# IMU-Module_v1_0.net
KiCad netlist of a schematic drawn in EAGLE
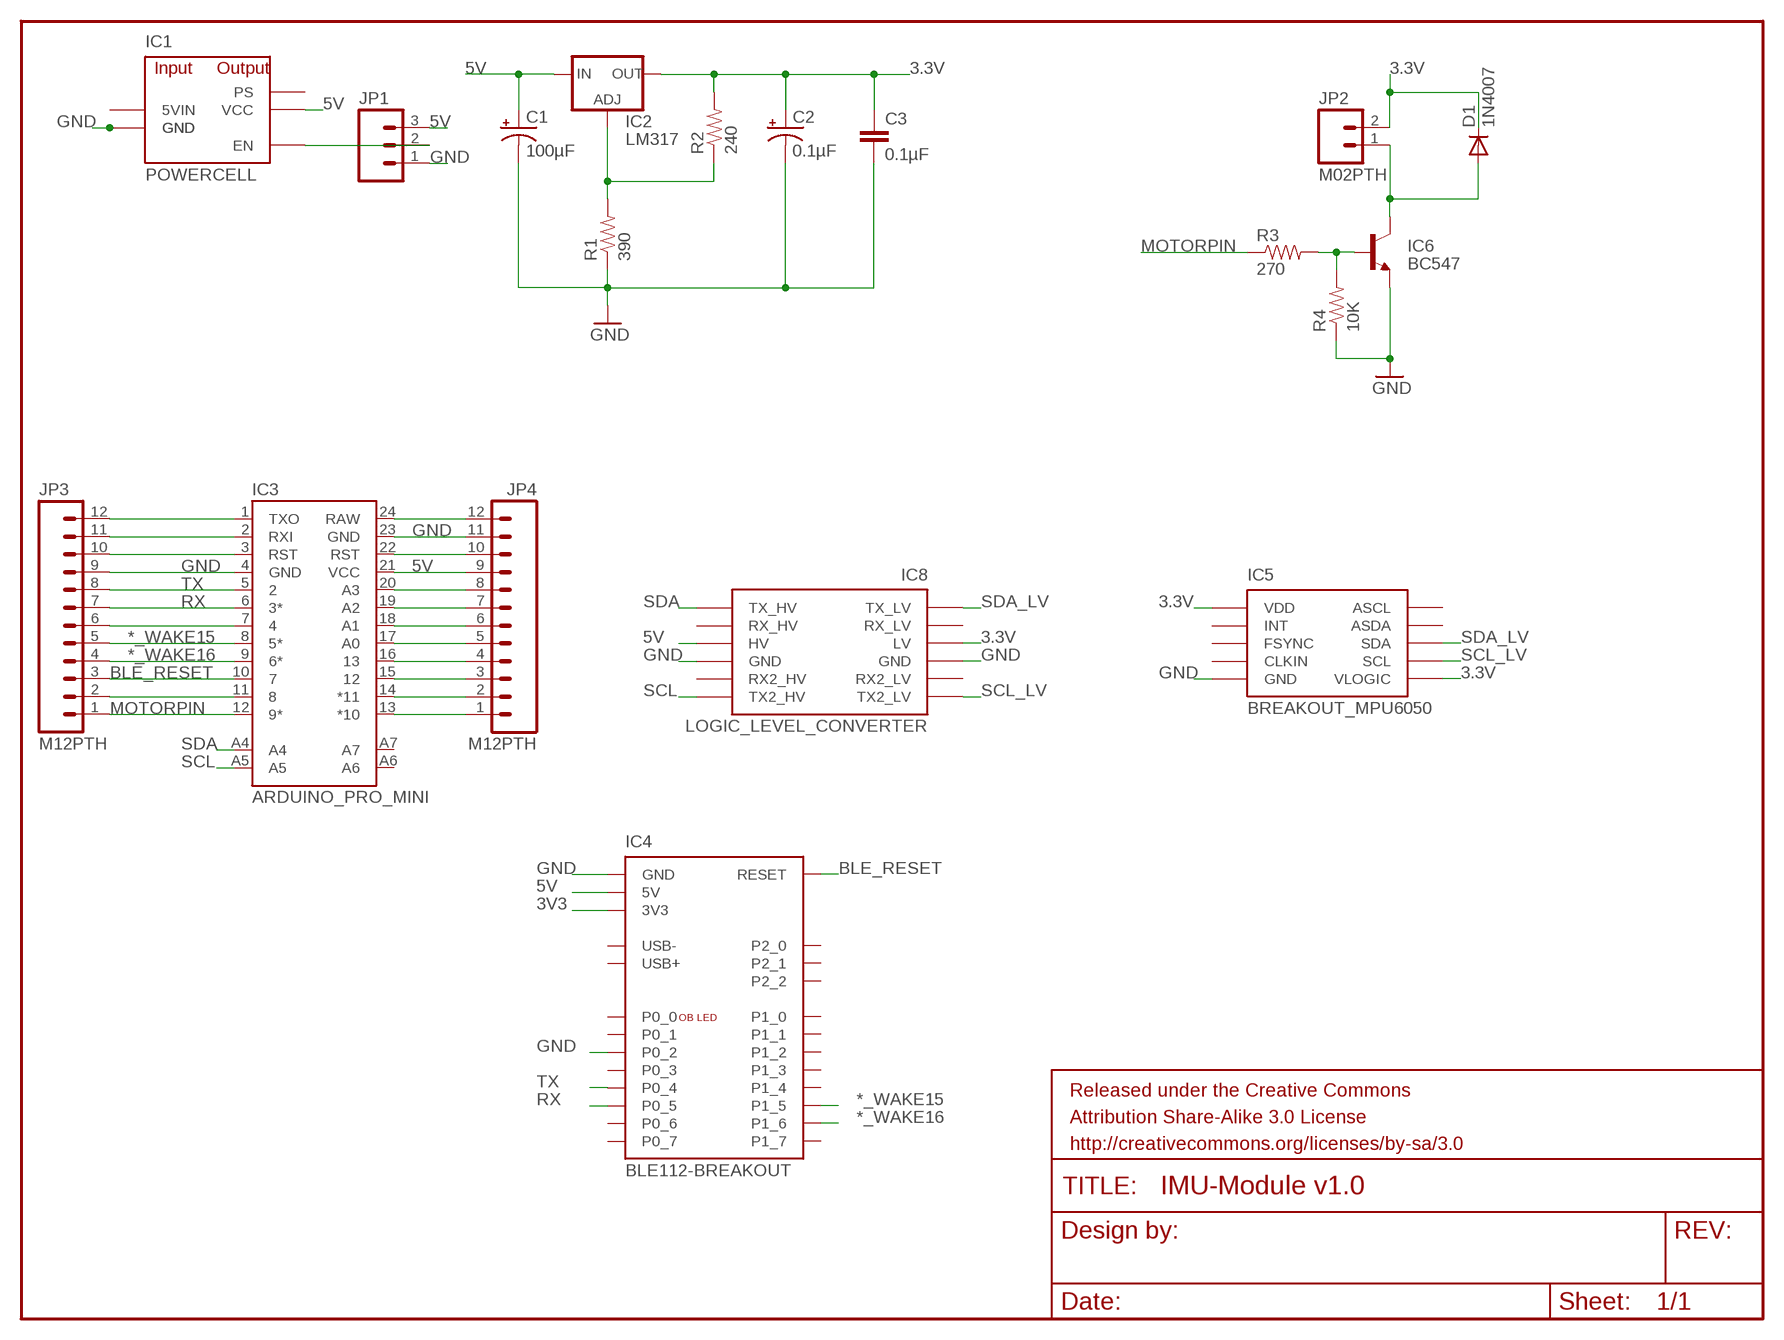
[diagram p0: schematic, sheet 1]

(export (version "E")
  (design (tool "Eeschema 10.0.6"))
  (components
    (comp (ref "C1")
      (value "100µF")
      (footprint "eagle-import:CPOL-RADIAL-100UF-25V")
      (libsource (lib "eagle-import") (part "CAP_POLPTH1"))
    )
    (comp (ref "C2")
      (value "0.1µF")
      (footprint "eagle-import:CPOL-RADIAL-10UF-25V")
      (libsource (lib "eagle-import") (part "CAP_POLPTH2"))
    )
    (comp (ref "C3")
      (value "0.1µF")
      (footprint "eagle-import:1206")
      (libsource (lib "eagle-import") (part "CAP1206"))
    )
    (comp (ref "D1")
      (value "1N4007")
      (footprint "eagle-import:DIODE-1N4001-KIT")
      (libsource (lib "eagle-import") (part "DIODE"))
    )
    (comp (ref "FRAME1")
      (value "FRAME-LETTER")
      (footprint "eagle-import:CREATIVE_COMMONS")
      (libsource (lib "eagle-import") (part "FRAME-LETTER"))
    )
    (comp (ref "IC1")
      (value "POWERCELL")
      (footprint "eagle-import:POWERCELL")
      (libsource (lib "eagle-import") (part "POWERCELL"))
    )
    (comp (ref "IC2")
      (value "LM317")
      (footprint "eagle-import:SOT223")
      (libsource (lib "eagle-import") (part "V_REG_317SMD"))
    )
    (comp (ref "IC3")
      (value "ARDUINO_PRO_MINI")
      (footprint "eagle-import:ARDUINO_PRO_MINI")
      (libsource (lib "eagle-import") (part "ARDUINO_PRO_MINI"))
    )
    (comp (ref "IC4")
      (value "BLE112-BREAKOUT")
      (footprint "eagle-import:BLE112-BREAKOUT")
      (libsource (lib "eagle-import") (part "BLE112-BREAKOUT"))
    )
    (comp (ref "IC5")
      (value "BREAKOUT_MPU6050")
      (footprint "eagle-import:BREAKOUT_MPU6050")
      (libsource (lib "eagle-import") (part "BREAKOUT_MPU6050"))
    )
    (comp (ref "IC6")
      (value "BC547")
      (footprint "eagle-import:TO-92")
      (libsource (lib "eagle-import") (part "BC547"))
    )
    (comp (ref "IC8")
      (value "LOGIC_LEVEL_CONVERTER")
      (footprint "eagle-import:LOGIC_LEVEL_CONVERTER")
      (libsource (lib "eagle-import") (part "LOGIC_LEVEL_CONVERTER"))
    )
    (comp (ref "JP1")
      (value "M03PTH")
      (footprint "eagle-import:1X03")
      (libsource (lib "eagle-import") (part "M03PTH"))
    )
    (comp (ref "JP2")
      (value "M02PTH")
      (footprint "eagle-import:1X02")
      (libsource (lib "eagle-import") (part "M02PTH"))
    )
    (comp (ref "JP3")
      (value "M12PTH")
      (footprint "eagle-import:1X12")
      (libsource (lib "eagle-import") (part "M12PTH"))
    )
    (comp (ref "JP4")
      (value "M12PTH")
      (footprint "eagle-import:1X12")
      (libsource (lib "eagle-import") (part "M12PTH"))
    )
    (comp (ref "R1")
      (value "390")
      (footprint "eagle-import:1206")
      (libsource (lib "eagle-import") (part "RESISTOR1206"))
    )
    (comp (ref "R2")
      (value "240")
      (footprint "eagle-import:1206")
      (libsource (lib "eagle-import") (part "RESISTOR1206"))
    )
    (comp (ref "R3")
      (value "270")
      (footprint "eagle-import:1206")
      (libsource (lib "eagle-import") (part "RESISTOR1206"))
    )
    (comp (ref "R4")
      (value "10K")
      (footprint "eagle-import:1206")
      (libsource (lib "eagle-import") (part "RESISTOR1206"))
    )
  )
  (nets
    (net (code "1") (name "/*_WAKE15") (class "Default")
      (node (ref "IC3") (pin "8") (pinfunction "5*_8") (pintype "bidirectional"))
      (node (ref "IC4") (pin "P15") (pinfunction "P1_5_P15") (pintype "bidirectional"))
      (node (ref "JP3") (pin "5") (pinfunction "5_5") (pintype "passive"))
    )
    (net (code "2") (name "/*_WAKE16") (class "Default")
      (node (ref "IC3") (pin "9") (pinfunction "6*_9") (pintype "bidirectional"))
      (node (ref "IC4") (pin "P16") (pinfunction "P1_6_P16") (pintype "bidirectional"))
      (node (ref "JP3") (pin "4") (pinfunction "4_4") (pintype "passive"))
    )
    (net (code "3") (name "/3.3V") (class "Default")
      (node (ref "C2") (pin "1") (pinfunction "+_1") (pintype "passive"))
      (node (ref "C3") (pin "1") (pinfunction "1_1") (pintype "passive"))
      (node (ref "D1") (pin "C") (pinfunction "C_C") (pintype "passive"))
      (node (ref "IC2") (pin "2") (pinfunction "OUT_2") (pintype "output"))
      (node (ref "IC5") (pin "VDD") (pinfunction "VDD_VDD") (pintype "power_in"))
      (node (ref "IC5") (pin "VLOGIC") (pinfunction "VLOGIC_VLOGIC") (pintype "bidirectional"))
      (node (ref "IC8") (pin "LV") (pinfunction "LV_LV") (pintype "power_in"))
      (node (ref "JP2") (pin "2") (pinfunction "2_2") (pintype "passive"))
      (node (ref "R2") (pin "2") (pinfunction "2_2") (pintype "passive"))
    )
    (net (code "4") (name "/3V3") (class "Default")
      (node (ref "IC4") (pin "3V3") (pinfunction "3V3_3V3") (pintype "power_in"))
    )
    (net (code "5") (name "/5V") (class "Default")
      (node (ref "C1") (pin "1") (pinfunction "+_1") (pintype "passive"))
      (node (ref "IC1") (pin "VCC") (pinfunction "VCC_VCC") (pintype "power_in"))
      (node (ref "IC2") (pin "3") (pinfunction "IN_3") (pintype "input"))
      (node (ref "IC3") (pin "21") (pinfunction "VCC_21") (pintype "bidirectional"))
      (node (ref "IC4") (pin "5V") (pinfunction "5V_5V") (pintype "power_in"))
      (node (ref "IC8") (pin "HV") (pinfunction "HV_HV") (pintype "power_in"))
      (node (ref "JP1") (pin "3") (pinfunction "3_3") (pintype "passive"))
      (node (ref "JP4") (pin "9") (pinfunction "9_9") (pintype "passive"))
    )
    (net (code "6") (name "/5VIN") (class "Default")
      (node (ref "IC1") (pin "5VIN") (pinfunction "5VIN_5VIN") (pintype "power_in"))
    )
    (net (code "7") (name "/BLE_RESET") (class "Default")
      (node (ref "IC3") (pin "10") (pinfunction "7_10") (pintype "bidirectional"))
      (node (ref "IC4") (pin "RESET") (pinfunction "RESET_RESET") (pintype "input"))
      (node (ref "JP3") (pin "3") (pinfunction "3_3") (pintype "passive"))
    )
    (net (code "8") (name "/MOTORPIN") (class "Default")
      (node (ref "IC3") (pin "12") (pinfunction "9*_12") (pintype "bidirectional"))
      (node (ref "JP3") (pin "1") (pinfunction "1_1") (pintype "passive"))
      (node (ref "R3") (pin "1") (pinfunction "1_1") (pintype "passive"))
    )
    (net (code "9") (name "/RX") (class "Default")
      (node (ref "IC3") (pin "6") (pinfunction "3*_6") (pintype "bidirectional"))
      (node (ref "IC4") (pin "P05") (pinfunction "P0_5_P05") (pintype "bidirectional"))
      (node (ref "JP3") (pin "7") (pinfunction "7_7") (pintype "passive"))
    )
    (net (code "10") (name "/RX2_HV") (class "Default")
      (node (ref "IC8") (pin "HV_RXI_2") (pinfunction "RX2_HV_HV_RXI_2") (pintype "power_in"))
    )
    (net (code "11") (name "/RX2_LV") (class "Default")
      (node (ref "IC8") (pin "LV_RXO_2") (pinfunction "RX2_LV_LV_RXO_2") (pintype "power_in"))
    )
    (net (code "12") (name "/RX_HV") (class "Default")
      (node (ref "IC8") (pin "HV_RXI_1") (pinfunction "RX_HV_HV_RXI_1") (pintype "power_in"))
    )
    (net (code "13") (name "/RX_LV") (class "Default")
      (node (ref "IC8") (pin "LV_RXO_1") (pinfunction "RX_LV_LV_RXO_1") (pintype "power_in"))
    )
    (net (code "14") (name "/SCL") (class "Default")
      (node (ref "IC3") (pin "A5") (pinfunction "A5_A5") (pintype "bidirectional"))
      (node (ref "IC8") (pin "HV_TXO_2") (pinfunction "TX2_HV_HV_TXO_2") (pintype "power_in"))
    )
    (net (code "15") (name "/SCL_LV") (class "Default")
      (node (ref "IC5") (pin "SCL") (pinfunction "SCL_SCL") (pintype "bidirectional"))
      (node (ref "IC8") (pin "LV_TXI_2") (pinfunction "TX2_LV_LV_TXI_2") (pintype "power_in"))
    )
    (net (code "16") (name "/SDA") (class "Default")
      (node (ref "IC3") (pin "A4") (pinfunction "A4_A4") (pintype "bidirectional"))
      (node (ref "IC8") (pin "HV_TXO_1") (pinfunction "TX_HV_HV_TXO_1") (pintype "power_in"))
    )
    (net (code "17") (name "/SDA_LV") (class "Default")
      (node (ref "IC5") (pin "SDA") (pinfunction "SDA_SDA") (pintype "bidirectional"))
      (node (ref "IC8") (pin "LV_TXI_1") (pinfunction "TX_LV_LV_TXI_1") (pintype "power_in"))
    )
    (net (code "18") (name "/TX") (class "Default")
      (node (ref "IC3") (pin "5") (pinfunction "2_5") (pintype "bidirectional"))
      (node (ref "IC4") (pin "P04") (pinfunction "P0_4_P04") (pintype "bidirectional"))
      (node (ref "JP3") (pin "8") (pinfunction "8_8") (pintype "passive"))
    )
    (net (code "19") (name "GND") (class "Default")
      (node (ref "C1") (pin "2") (pinfunction "-_2") (pintype "passive"))
      (node (ref "C2") (pin "2") (pinfunction "-_2") (pintype "passive"))
      (node (ref "C3") (pin "2") (pinfunction "2_2") (pintype "passive"))
      (node (ref "IC1") (pin "GND@1") (pinfunction "GND_GND@1") (pintype "power_in"))
      (node (ref "IC1") (pin "GND@2") (pinfunction "GND_GND@2") (pintype "power_in"))
      (node (ref "IC3") (pin "23") (pinfunction "GND_23") (pintype "bidirectional"))
      (node (ref "IC3") (pin "4") (pinfunction "GND_4") (pintype "bidirectional"))
      (node (ref "IC4") (pin "GND") (pinfunction "GND_GND") (pintype "power_in"))
      (node (ref "IC4") (pin "P02") (pinfunction "P0_2_P02") (pintype "bidirectional"))
      (node (ref "IC5") (pin "GND") (pinfunction "GND_GND") (pintype "power_in"))
      (node (ref "IC6") (pin "3") (pinfunction "E_3") (pintype "passive"))
      (node (ref "IC8") (pin "GND@1") (pinfunction "GND_GND@1") (pintype "power_in"))
      (node (ref "IC8") (pin "GND@2") (pinfunction "GND_GND@2") (pintype "power_in"))
      (node (ref "JP1") (pin "1") (pinfunction "1_1") (pintype "passive"))
      (node (ref "JP3") (pin "9") (pinfunction "9_9") (pintype "passive"))
      (node (ref "JP4") (pin "11") (pinfunction "11_11") (pintype "passive"))
      (node (ref "R1") (pin "1") (pinfunction "1_1") (pintype "passive"))
      (node (ref "R4") (pin "1") (pinfunction "1_1") (pintype "passive"))
    )
    (net (code "20") (name "Net-(IC1-PadEN)") (class "Default")
      (node (ref "IC1") (pin "EN") (pinfunction "EN_EN") (pintype "bidirectional"))
      (node (ref "JP1") (pin "2") (pinfunction "2_2") (pintype "passive"))
    )
    (net (code "21") (name "Net-(IC2-ADJ)") (class "Default")
      (node (ref "IC2") (pin "1") (pinfunction "ADJ_1") (pintype "input"))
      (node (ref "R1") (pin "2") (pinfunction "2_2") (pintype "passive"))
      (node (ref "R2") (pin "1") (pinfunction "1_1") (pintype "passive"))
    )
    (net (code "22") (name "Net-(IC3-*10)") (class "Default")
      (node (ref "IC3") (pin "13") (pinfunction "*10_13") (pintype "bidirectional"))
      (node (ref "JP4") (pin "1") (pinfunction "1_1") (pintype "passive"))
    )
    (net (code "23") (name "Net-(IC3-*11)") (class "Default")
      (node (ref "IC3") (pin "14") (pinfunction "*11_14") (pintype "bidirectional"))
      (node (ref "JP4") (pin "2") (pinfunction "2_2") (pintype "passive"))
    )
    (net (code "24") (name "Net-(IC3-4)") (class "Default")
      (node (ref "IC3") (pin "7") (pinfunction "4_7") (pintype "bidirectional"))
      (node (ref "JP3") (pin "6") (pinfunction "6_6") (pintype "passive"))
    )
    (net (code "25") (name "Net-(IC3-8)") (class "Default")
      (node (ref "IC3") (pin "11") (pinfunction "8_11") (pintype "bidirectional"))
      (node (ref "JP3") (pin "2") (pinfunction "2_2") (pintype "passive"))
    )
    (net (code "26") (name "Net-(IC3-12)") (class "Default")
      (node (ref "IC3") (pin "15") (pinfunction "12_15") (pintype "bidirectional"))
      (node (ref "JP4") (pin "3") (pinfunction "3_3") (pintype "passive"))
    )
    (net (code "27") (name "Net-(IC3-13)") (class "Default")
      (node (ref "IC3") (pin "16") (pinfunction "13_16") (pintype "bidirectional"))
      (node (ref "JP4") (pin "4") (pinfunction "4_4") (pintype "passive"))
    )
    (net (code "28") (name "Net-(IC3-A0)") (class "Default")
      (node (ref "IC3") (pin "17") (pinfunction "A0_17") (pintype "bidirectional"))
      (node (ref "JP4") (pin "5") (pinfunction "5_5") (pintype "passive"))
    )
    (net (code "29") (name "Net-(IC3-A1)") (class "Default")
      (node (ref "IC3") (pin "18") (pinfunction "A1_18") (pintype "bidirectional"))
      (node (ref "JP4") (pin "6") (pinfunction "6_6") (pintype "passive"))
    )
    (net (code "30") (name "Net-(IC3-A2)") (class "Default")
      (node (ref "IC3") (pin "19") (pinfunction "A2_19") (pintype "bidirectional"))
      (node (ref "JP4") (pin "7") (pinfunction "7_7") (pintype "passive"))
    )
    (net (code "31") (name "Net-(IC3-A3)") (class "Default")
      (node (ref "IC3") (pin "20") (pinfunction "A3_20") (pintype "bidirectional"))
      (node (ref "JP4") (pin "8") (pinfunction "8_8") (pintype "passive"))
    )
    (net (code "32") (name "Net-(IC3-RAW)") (class "Default")
      (node (ref "IC3") (pin "24") (pinfunction "RAW_24") (pintype "bidirectional"))
      (node (ref "JP4") (pin "12") (pinfunction "12_12") (pintype "passive"))
    )
    (net (code "33") (name "Net-(IC3-RST-Pad3)") (class "Default")
      (node (ref "IC3") (pin "3") (pinfunction "RST_3") (pintype "bidirectional"))
      (node (ref "JP3") (pin "10") (pinfunction "10_10") (pintype "passive"))
    )
    (net (code "34") (name "Net-(IC3-RST-Pad22)") (class "Default")
      (node (ref "IC3") (pin "22") (pinfunction "RST_22") (pintype "bidirectional"))
      (node (ref "JP4") (pin "10") (pinfunction "10_10") (pintype "passive"))
    )
    (net (code "35") (name "Net-(IC3-RXI)") (class "Default")
      (node (ref "IC3") (pin "2") (pinfunction "RXI_2") (pintype "bidirectional"))
      (node (ref "JP3") (pin "11") (pinfunction "11_11") (pintype "passive"))
    )
    (net (code "36") (name "Net-(IC3-TXO)") (class "Default")
      (node (ref "IC3") (pin "1") (pinfunction "TXO_1") (pintype "bidirectional"))
      (node (ref "JP3") (pin "12") (pinfunction "12_12") (pintype "passive"))
    )
    (net (code "37") (name "Net-(IC6-B)") (class "Default")
      (node (ref "IC6") (pin "2") (pinfunction "B_2") (pintype "passive"))
      (node (ref "R3") (pin "2") (pinfunction "2_2") (pintype "passive"))
      (node (ref "R4") (pin "2") (pinfunction "2_2") (pintype "passive"))
    )
    (net (code "38") (name "Net-(IC6-C)") (class "Default")
      (node (ref "D1") (pin "A") (pinfunction "A_A") (pintype "passive"))
      (node (ref "IC6") (pin "1") (pinfunction "C_1") (pintype "passive"))
      (node (ref "JP2") (pin "1") (pinfunction "1_1") (pintype "passive"))
    )
    (net (code "39") (name "unconnected-(IC1-PadPS)") (class "Default")
      (node (ref "IC1") (pin "PS") (pinfunction "PS_PS") (pintype "bidirectional"))
    )
    (net (code "40") (name "unconnected-(IC3-PadA6)") (class "Default")
      (node (ref "IC3") (pin "A6") (pinfunction "A6_A6") (pintype "bidirectional"))
    )
    (net (code "41") (name "unconnected-(IC3-PadA7)") (class "Default")
      (node (ref "IC3") (pin "A7") (pinfunction "A7_A7") (pintype "bidirectional"))
    )
    (net (code "42") (name "unconnected-(IC4-P0_0-PadP00)") (class "Default")
      (node (ref "IC4") (pin "P00") (pinfunction "P0_0_P00") (pintype "bidirectional"))
    )
    (net (code "43") (name "unconnected-(IC4-P0_1-PadP01)") (class "Default")
      (node (ref "IC4") (pin "P01") (pinfunction "P0_1_P01") (pintype "bidirectional"))
    )
    (net (code "44") (name "unconnected-(IC4-P0_3-PadP03)") (class "Default")
      (node (ref "IC4") (pin "P03") (pinfunction "P0_3_P03") (pintype "bidirectional"))
    )
    (net (code "45") (name "unconnected-(IC4-P0_6-PadP06)") (class "Default")
      (node (ref "IC4") (pin "P06") (pinfunction "P0_6_P06") (pintype "bidirectional"))
    )
    (net (code "46") (name "unconnected-(IC4-P0_7-PadP07)") (class "Default")
      (node (ref "IC4") (pin "P07") (pinfunction "P0_7_P07") (pintype "bidirectional"))
    )
    (net (code "47") (name "unconnected-(IC4-P1_0-PadP10)") (class "Default")
      (node (ref "IC4") (pin "P10") (pinfunction "P1_0_P10") (pintype "bidirectional"))
    )
    (net (code "48") (name "unconnected-(IC4-P1_1-PadP11)") (class "Default")
      (node (ref "IC4") (pin "P11") (pinfunction "P1_1_P11") (pintype "bidirectional"))
    )
    (net (code "49") (name "unconnected-(IC4-P1_2-PadP12)") (class "Default")
      (node (ref "IC4") (pin "P12") (pinfunction "P1_2_P12") (pintype "bidirectional"))
    )
    (net (code "50") (name "unconnected-(IC4-P1_3-PadP13)") (class "Default")
      (node (ref "IC4") (pin "P13") (pinfunction "P1_3_P13") (pintype "bidirectional"))
    )
    (net (code "51") (name "unconnected-(IC4-P1_4-PadP14)") (class "Default")
      (node (ref "IC4") (pin "P14") (pinfunction "P1_4_P14") (pintype "bidirectional"))
    )
    (net (code "52") (name "unconnected-(IC4-P1_7-PadP17)") (class "Default")
      (node (ref "IC4") (pin "P17") (pinfunction "P1_7_P17") (pintype "bidirectional"))
    )
    (net (code "53") (name "unconnected-(IC4-P2_0-PadP20)") (class "Default")
      (node (ref "IC4") (pin "P20") (pinfunction "P2_0_P20") (pintype "bidirectional"))
    )
    (net (code "54") (name "unconnected-(IC4-P2_1-PadP21)") (class "Default")
      (node (ref "IC4") (pin "P21") (pinfunction "P2_1_P21") (pintype "bidirectional"))
    )
    (net (code "55") (name "unconnected-(IC4-P2_2-PadP22)") (class "Default")
      (node (ref "IC4") (pin "P22") (pinfunction "P2_2_P22") (pintype "bidirectional"))
    )
    (net (code "56") (name "unconnected-(IC4-PadUSB+)") (class "Default")
      (node (ref "IC4") (pin "USB+") (pinfunction "USB+_USB+") (pintype "bidirectional"))
    )
    (net (code "57") (name "unconnected-(IC4-PadUSB-)") (class "Default")
      (node (ref "IC4") (pin "USB-") (pinfunction "USB-_USB-") (pintype "bidirectional"))
    )
    (net (code "58") (name "unconnected-(IC5-CLKIN-PadCLK)") (class "Default")
      (node (ref "IC5") (pin "CLK") (pinfunction "CLKIN_CLK") (pintype "bidirectional"))
    )
    (net (code "59") (name "unconnected-(IC5-PadASCL)") (class "Default")
      (node (ref "IC5") (pin "ASCL") (pinfunction "ASCL_ASCL") (pintype "bidirectional"))
    )
    (net (code "60") (name "unconnected-(IC5-PadASDA)") (class "Default")
      (node (ref "IC5") (pin "ASDA") (pinfunction "ASDA_ASDA") (pintype "bidirectional"))
    )
    (net (code "61") (name "unconnected-(IC5-PadFSYNC)") (class "Default")
      (node (ref "IC5") (pin "FSYNC") (pinfunction "FSYNC_FSYNC") (pintype "bidirectional"))
    )
    (net (code "62") (name "unconnected-(IC5-PadINT)") (class "Default")
      (node (ref "IC5") (pin "INT") (pinfunction "INT_INT") (pintype "bidirectional"))
    )
  )
)
